# akabeacon_square_type2_da14580.net
KiCad netlist of a schematic drawn in EAGLE
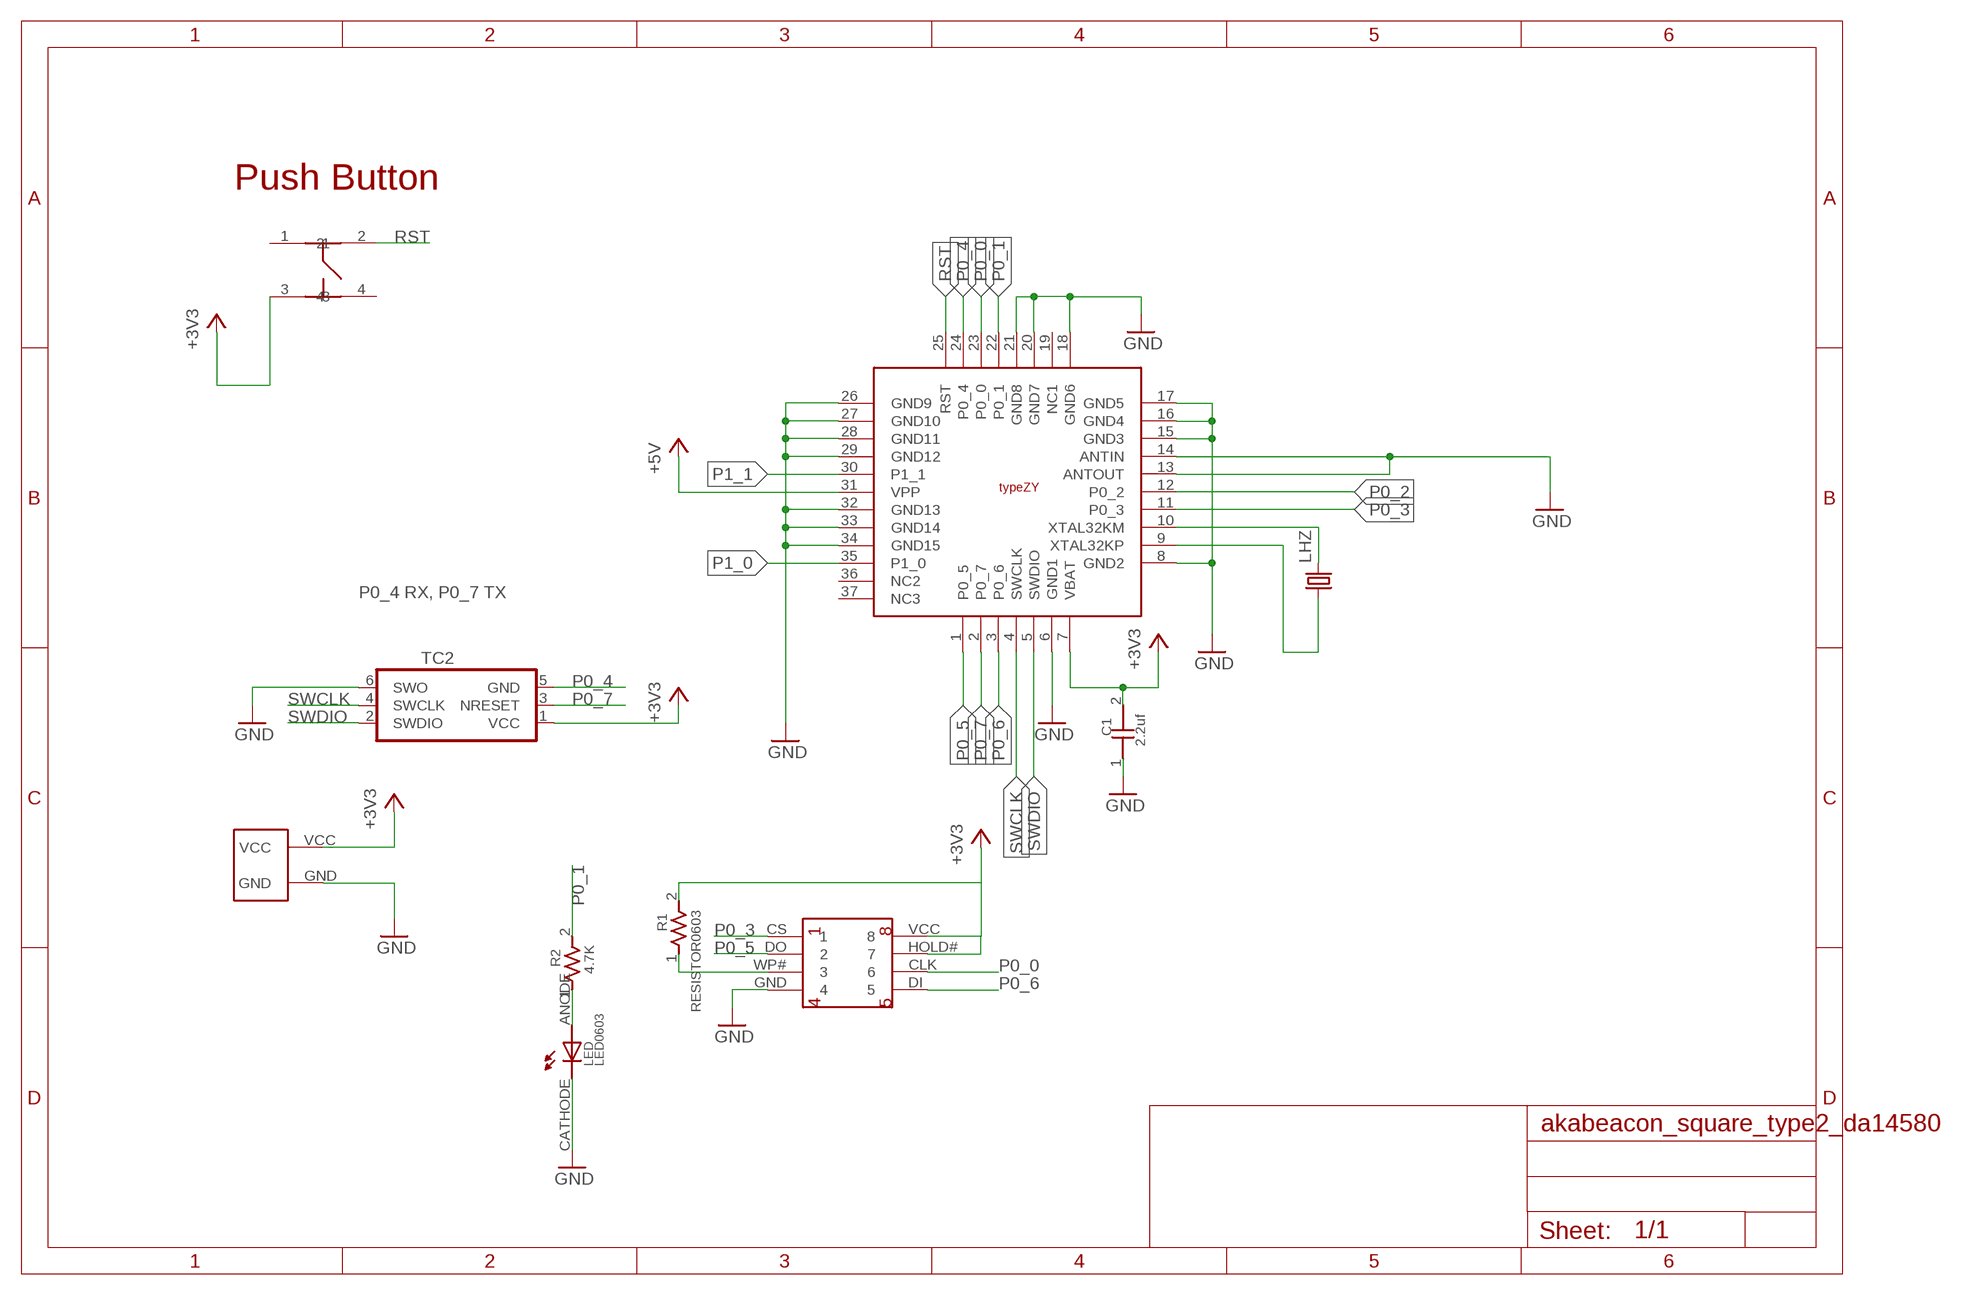
[diagram p0: schematic, sheet 1]

(export (version "E")
  (design (tool "Eeschema 10.0.6"))
  (components
    (comp (ref "C1")
      (value "2.2uf")
      (footprint "eagle-import:0603")
      (libsource (lib "eagle-import") (part "CAPACITOR0603"))
    )
    (comp (ref "LED")
      (value "LED0603")
      (footprint "eagle-import:0603")
      (libsource (lib "eagle-import") (part "LED0603"))
    )
    (comp (ref "LHZ")
      (value "FC-12M")
      (footprint "eagle-import:FC-12M")
      (libsource (lib "eagle-import") (part "FC-12M"))
    )
    (comp (ref "R1")
      (value "RESISTOR0603")
      (footprint "eagle-import:0603")
      (libsource (lib "eagle-import") (part "RESISTOR0603"))
    )
    (comp (ref "R2")
      (value "4.7K")
      (footprint "eagle-import:0603")
      (libsource (lib "eagle-import") (part "RESISTOR0603"))
    )
    (comp (ref "TC2")
      (value "TC2030-IDC-NL")
      (footprint "eagle-import:TC2030-IDC-NL")
      (libsource (lib "eagle-import") (part "TC2030-IDC-NL"))
    )
    (comp (ref "U$3")
      (value "FLASH-MEMORY-2M(WINBOND)")
      (footprint "eagle-import:FLASH-MEMORY-2M(WINBOND)")
      (libsource (lib "eagle-import") (part "FLASH-MEMORY-2M(WINBOND)"))
    )
    (comp (ref "U$5")
      (value "SQUARE-TYPE2-TC2030")
      (footprint "eagle-import:SQUARE-TYPE2-TC2030")
      (libsource (lib "eagle-import") (part "SQUARE-TYPE2-TC2030"))
    )
    (comp (ref "U$7")
      (value "SWICTH-4P(KMR2)")
      (footprint "eagle-import:SWITCH-4P(KMR2)")
      (libsource (lib "eagle-import") (part "SWICTH-4P(KMR2)"))
    )
    (comp (ref "U$9")
      (value "MURATA-TYPEZY")
      (footprint "eagle-import:MURATA_TYPEZY")
      (libsource (lib "eagle-import") (part "MURATA-TYPEZY"))
    )
  )
  (nets
    (net (code "1") (name "+3V3") (class "Default")
      (node (ref "C1") (pin "2") (pinfunction "2_2") (pintype "passive"))
      (node (ref "R1") (pin "2") (pinfunction "2_2") (pintype "passive"))
      (node (ref "TC2") (pin "1") (pinfunction "VCC_1") (pintype "passive"))
      (node (ref "U$3") (pin "HOLD#") (pinfunction "7_HOLD#") (pintype "bidirectional"))
      (node (ref "U$3") (pin "VCC") (pinfunction "8_VCC") (pintype "bidirectional"))
      (node (ref "U$5") (pin "VCC") (pinfunction "VCC_VCC") (pintype "bidirectional"))
      (node (ref "U$7") (pin "3") (pinfunction "3_3") (pintype "bidirectional"))
      (node (ref "U$9") (pin "7") (pinfunction "VBAT_7") (pintype "bidirectional"))
    )
    (net (code "2") (name "+5V") (class "Default")
      (node (ref "U$9") (pin "31") (pinfunction "VPP_31") (pintype "bidirectional"))
    )
    (net (code "3") (name "GND") (class "Default")
      (node (ref "C1") (pin "1") (pinfunction "1_1") (pintype "passive"))
      (node (ref "LED") (pin "CATHODE") (pinfunction "CATHODE_CATHODE") (pintype "passive"))
      (node (ref "TC2") (pin "6") (pinfunction "SWO_6") (pintype "passive"))
      (node (ref "U$3") (pin "GND") (pinfunction "4_GND") (pintype "bidirectional"))
      (node (ref "U$5") (pin "GND") (pinfunction "GND_GND") (pintype "bidirectional"))
      (node (ref "U$9") (pin "13") (pinfunction "ANTOUT_13") (pintype "bidirectional"))
      (node (ref "U$9") (pin "14") (pinfunction "ANTIN_14") (pintype "bidirectional"))
      (node (ref "U$9") (pin "15") (pinfunction "GND3_15") (pintype "bidirectional"))
      (node (ref "U$9") (pin "16") (pinfunction "GND4_16") (pintype "bidirectional"))
      (node (ref "U$9") (pin "17") (pinfunction "GND5_17") (pintype "bidirectional"))
      (node (ref "U$9") (pin "18") (pinfunction "GND6_18") (pintype "bidirectional"))
      (node (ref "U$9") (pin "20") (pinfunction "GND7_20") (pintype "bidirectional"))
      (node (ref "U$9") (pin "21") (pinfunction "GND8_21") (pintype "bidirectional"))
      (node (ref "U$9") (pin "26") (pinfunction "GND9_26") (pintype "bidirectional"))
      (node (ref "U$9") (pin "27") (pinfunction "GND10_27") (pintype "bidirectional"))
      (node (ref "U$9") (pin "28") (pinfunction "GND11_28") (pintype "bidirectional"))
      (node (ref "U$9") (pin "29") (pinfunction "GND12_29") (pintype "bidirectional"))
      (node (ref "U$9") (pin "32") (pinfunction "GND13_32") (pintype "bidirectional"))
      (node (ref "U$9") (pin "33") (pinfunction "GND14_33") (pintype "bidirectional"))
      (node (ref "U$9") (pin "34") (pinfunction "GND15_34") (pintype "bidirectional"))
      (node (ref "U$9") (pin "6") (pinfunction "GND1_6") (pintype "bidirectional"))
      (node (ref "U$9") (pin "8") (pinfunction "GND2_8") (pintype "bidirectional"))
    )
    (net (code "4") (name "Net-(LED-PadANODE)") (class "Default")
      (node (ref "LED") (pin "ANODE") (pinfunction "ANODE_ANODE") (pintype "passive"))
      (node (ref "R2") (pin "1") (pinfunction "1_1") (pintype "passive"))
    )
    (net (code "5") (name "Net-(U$3-3)") (class "Default")
      (node (ref "R1") (pin "1") (pinfunction "1_1") (pintype "passive"))
      (node (ref "U$3") (pin "WP#") (pinfunction "3_WP#") (pintype "bidirectional"))
    )
    (net (code "6") (name "Net-(U$9-XTAL32KM)") (class "Default")
      (node (ref "LHZ") (pin "2") (pinfunction "2_2") (pintype "passive"))
      (node (ref "U$9") (pin "10") (pinfunction "XTAL32KM_10") (pintype "bidirectional"))
    )
    (net (code "7") (name "Net-(U$9-XTAL32KP)") (class "Default")
      (node (ref "LHZ") (pin "1") (pinfunction "1_1") (pintype "passive"))
      (node (ref "U$9") (pin "9") (pinfunction "XTAL32KP_9") (pintype "bidirectional"))
    )
    (net (code "8") (name "P0_0") (class "Default")
      (node (ref "U$3") (pin "CLK") (pinfunction "6_CLK") (pintype "bidirectional"))
      (node (ref "U$9") (pin "23") (pinfunction "P0_0_23") (pintype "bidirectional"))
    )
    (net (code "9") (name "P0_1") (class "Default")
      (node (ref "R2") (pin "2") (pinfunction "2_2") (pintype "passive"))
      (node (ref "U$9") (pin "22") (pinfunction "P0_1_22") (pintype "bidirectional"))
    )
    (net (code "10") (name "P0_2") (class "Default")
      (node (ref "U$9") (pin "12") (pinfunction "P0_2_12") (pintype "bidirectional"))
    )
    (net (code "11") (name "P0_3") (class "Default")
      (node (ref "U$3") (pin "CS") (pinfunction "1_CS") (pintype "bidirectional"))
      (node (ref "U$9") (pin "11") (pinfunction "P0_3_11") (pintype "bidirectional"))
    )
    (net (code "12") (name "P0_4") (class "Default")
      (node (ref "TC2") (pin "5") (pinfunction "GND_5") (pintype "passive"))
      (node (ref "U$9") (pin "24") (pinfunction "P0_4_24") (pintype "bidirectional"))
    )
    (net (code "13") (name "P0_5") (class "Default")
      (node (ref "U$3") (pin "DO") (pinfunction "2_DO") (pintype "bidirectional"))
      (node (ref "U$9") (pin "1") (pinfunction "P0_5_1") (pintype "bidirectional"))
    )
    (net (code "14") (name "P0_6") (class "Default")
      (node (ref "U$3") (pin "DI") (pinfunction "5_DI") (pintype "bidirectional"))
      (node (ref "U$9") (pin "3") (pinfunction "P0_6_3") (pintype "bidirectional"))
    )
    (net (code "15") (name "P0_7") (class "Default")
      (node (ref "TC2") (pin "3") (pinfunction "NRESET_3") (pintype "passive"))
      (node (ref "U$9") (pin "2") (pinfunction "P0_7_2") (pintype "bidirectional"))
    )
    (net (code "16") (name "P1_0") (class "Default")
      (node (ref "U$9") (pin "35") (pinfunction "P1_0_35") (pintype "bidirectional"))
    )
    (net (code "17") (name "P1_1") (class "Default")
      (node (ref "U$9") (pin "30") (pinfunction "P1_1_30") (pintype "bidirectional"))
    )
    (net (code "18") (name "RST") (class "Default")
      (node (ref "U$7") (pin "2") (pinfunction "2_2") (pintype "bidirectional"))
      (node (ref "U$9") (pin "25") (pinfunction "RST_25") (pintype "bidirectional"))
    )
    (net (code "19") (name "SWCLK") (class "Default")
      (node (ref "TC2") (pin "4") (pinfunction "SWCLK_4") (pintype "passive"))
      (node (ref "U$9") (pin "4") (pinfunction "SWCLK_4") (pintype "bidirectional"))
    )
    (net (code "20") (name "SWDIO") (class "Default")
      (node (ref "TC2") (pin "2") (pinfunction "SWDIO_2") (pintype "passive"))
      (node (ref "U$9") (pin "5") (pinfunction "SWDIO_5") (pintype "bidirectional"))
    )
    (net (code "21") (name "unconnected-(U$7-Pad1)") (class "Default")
      (node (ref "U$7") (pin "1") (pinfunction "1_1") (pintype "bidirectional"))
    )
    (net (code "22") (name "unconnected-(U$7-Pad4)") (class "Default")
      (node (ref "U$7") (pin "4") (pinfunction "4_4") (pintype "bidirectional"))
    )
    (net (code "23") (name "unconnected-(U$9-NC1-Pad19)") (class "Default")
      (node (ref "U$9") (pin "19") (pinfunction "NC1_19") (pintype "bidirectional"))
    )
    (net (code "24") (name "unconnected-(U$9-NC2-Pad36)") (class "Default")
      (node (ref "U$9") (pin "36") (pinfunction "NC2_36") (pintype "bidirectional"))
    )
    (net (code "25") (name "unconnected-(U$9-NC3-Pad37)") (class "Default")
      (node (ref "U$9") (pin "37") (pinfunction "NC3_37") (pintype "bidirectional"))
    )
  )
)
